# HokuyoPoE.net
KiCad netlist of a schematic drawn in EAGLE
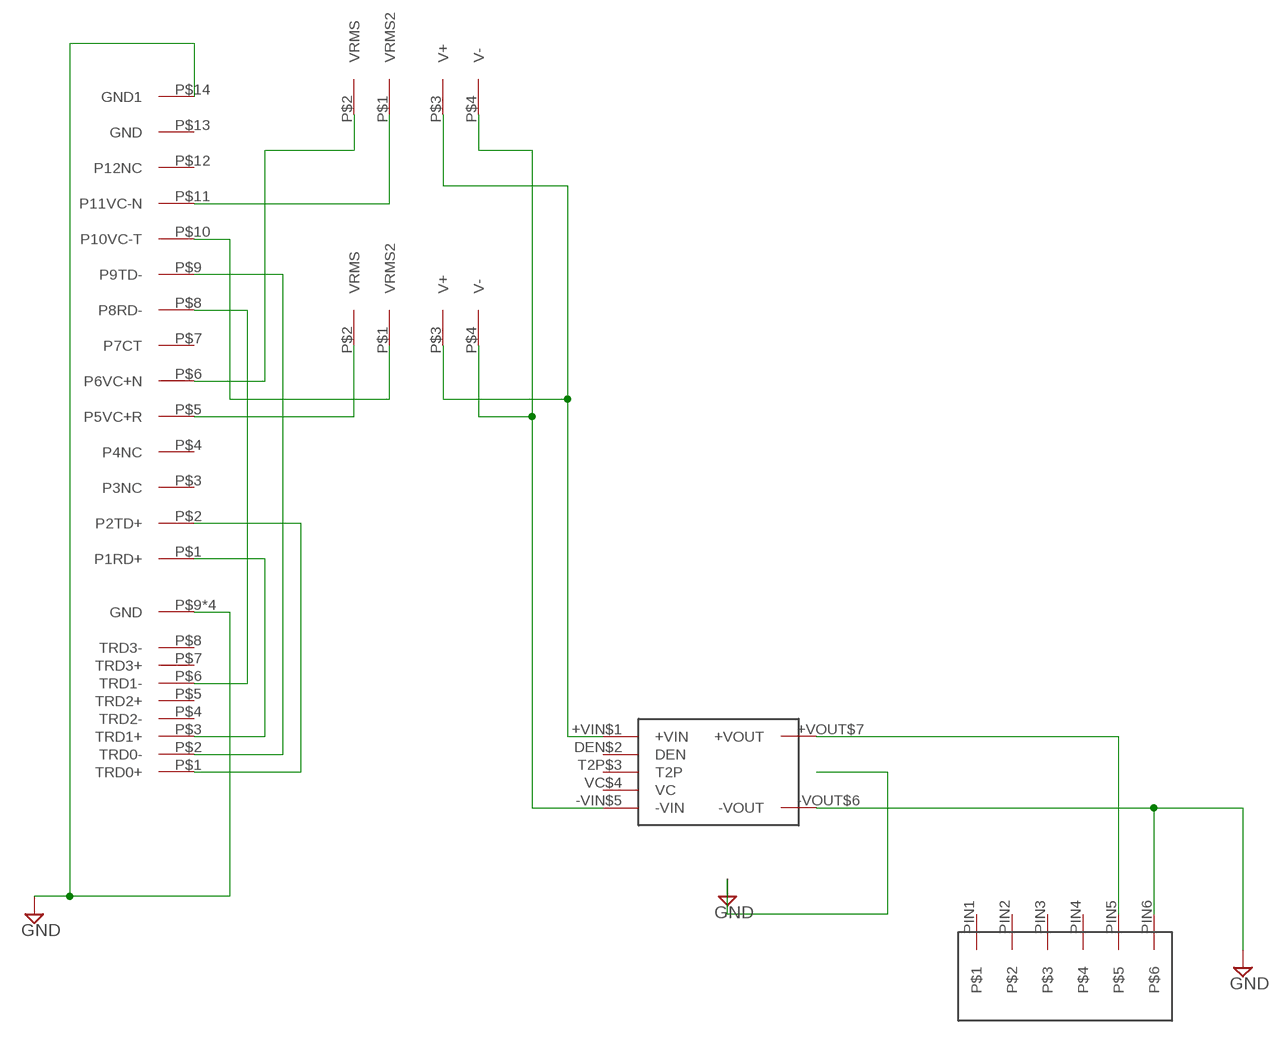
[diagram p0: schematic, sheet 1]

(export (version "E")
  (design (tool "Eeschema 10.0.6"))
  (components
    (comp (ref "U$1")
      (value "MYBSP0122BABFT")
      (footprint "eagle-import:MYBSP0122BABFT")
      (libsource (lib "eagle-import") (part "MYBSP0122BABFT"))
    )
    (comp (ref "U$2")
      (value "7810-XPXC[RJ45]")
      (footprint "eagle-import:7810-XPXC[RJ45]")
      (libsource (lib "eagle-import") (part "7810-XPXC[RJ45]"))
    )
    (comp (ref "U$3")
      (value "B1010S")
      (footprint "eagle-import:B1010S")
      (libsource (lib "eagle-import") (part "B1010S"))
    )
    (comp (ref "U$4")
      (value "SM08B-SRSS-TB")
      (footprint "eagle-import:SM08B-SRSS-TB")
      (libsource (lib "eagle-import") (part "SM08B-SRSS-TB"))
    )
    (comp (ref "U$5")
      (value "0813-1X1T-57-F")
      (footprint "eagle-import:0813-1X1T-57-F")
      (libsource (lib "eagle-import") (part "0813-1X1T-57-F"))
    )
    (comp (ref "U$6")
      (value "B1010S")
      (footprint "eagle-import:B1010S")
      (libsource (lib "eagle-import") (part "B1010S"))
    )
  )
  (nets
    (net (code "1") (name "GND") (class "Default")
      (node (ref "U$1") (pin "-VOUT$6") (pinfunction "-VOUT_-VOUT$6") (pintype "input"))
      (node (ref "U$2") (pin "P$10") (pinfunction "GND_P$10") (pintype "bidirectional"))
      (node (ref "U$2") (pin "P$11") (pinfunction "GND_P$11") (pintype "bidirectional"))
      (node (ref "U$2") (pin "P$12") (pinfunction "GND_P$12") (pintype "bidirectional"))
      (node (ref "U$2") (pin "P$9") (pinfunction "GND_P$9") (pintype "bidirectional"))
      (node (ref "U$4") (pin "PIN6") (pinfunction "P$6_PIN6") (pintype "bidirectional"))
      (node (ref "U$5") (pin "P$14") (pinfunction "GND1_P$14") (pintype "bidirectional"))
    )
    (net (code "2") (name "Net-(U$1-+VIN)") (class "Default")
      (node (ref "U$1") (pin "+VIN$1") (pinfunction "+VIN_+VIN$1") (pintype "input"))
      (node (ref "U$3") (pin "P$3") (pinfunction "V+_P$3") (pintype "bidirectional"))
      (node (ref "U$6") (pin "P$3") (pinfunction "V+_P$3") (pintype "bidirectional"))
    )
    (net (code "3") (name "Net-(U$1-+VOUT)") (class "Default")
      (node (ref "U$1") (pin "+VOUT$7") (pinfunction "+VOUT_+VOUT$7") (pintype "output"))
      (node (ref "U$4") (pin "PIN5") (pinfunction "P$5_PIN5") (pintype "bidirectional"))
    )
    (net (code "4") (name "Net-(U$1--VIN)") (class "Default")
      (node (ref "U$1") (pin "-VIN$5") (pinfunction "-VIN_-VIN$5") (pintype "input"))
      (node (ref "U$3") (pin "P$4") (pinfunction "V-_P$4") (pintype "bidirectional"))
      (node (ref "U$6") (pin "P$4") (pinfunction "V-_P$4") (pintype "bidirectional"))
    )
    (net (code "5") (name "Net-(U$2-TRD0+)") (class "Default")
      (node (ref "U$2") (pin "P$1") (pinfunction "TRD0+_P$1") (pintype "bidirectional"))
      (node (ref "U$5") (pin "P$2") (pinfunction "P2TD+_P$2") (pintype "bidirectional"))
    )
    (net (code "6") (name "Net-(U$2-TRD0-)") (class "Default")
      (node (ref "U$2") (pin "P$2") (pinfunction "TRD0-_P$2") (pintype "bidirectional"))
      (node (ref "U$5") (pin "P$9") (pinfunction "P9TD-_P$9") (pintype "bidirectional"))
    )
    (net (code "7") (name "Net-(U$2-TRD1+)") (class "Default")
      (node (ref "U$2") (pin "P$3") (pinfunction "TRD1+_P$3") (pintype "bidirectional"))
      (node (ref "U$5") (pin "P$1") (pinfunction "P1RD+_P$1") (pintype "bidirectional"))
    )
    (net (code "8") (name "Net-(U$2-TRD1-)") (class "Default")
      (node (ref "U$2") (pin "P$6") (pinfunction "TRD1-_P$6") (pintype "bidirectional"))
      (node (ref "U$5") (pin "P$8") (pinfunction "P8RD-_P$8") (pintype "bidirectional"))
    )
    (net (code "9") (name "Net-(U$3-VRMS)") (class "Default")
      (node (ref "U$3") (pin "P$2") (pinfunction "VRMS_P$2") (pintype "bidirectional"))
      (node (ref "U$5") (pin "P$6") (pinfunction "P6VC+N_P$6") (pintype "bidirectional"))
    )
    (net (code "10") (name "Net-(U$3-VRMS2)") (class "Default")
      (node (ref "U$3") (pin "P$1") (pinfunction "VRMS2_P$1") (pintype "bidirectional"))
      (node (ref "U$5") (pin "P$11") (pinfunction "P11VC-N_P$11") (pintype "bidirectional"))
    )
    (net (code "11") (name "Net-(U$5-P5VC+R)") (class "Default")
      (node (ref "U$5") (pin "P$5") (pinfunction "P5VC+R_P$5") (pintype "bidirectional"))
      (node (ref "U$6") (pin "P$2") (pinfunction "VRMS_P$2") (pintype "bidirectional"))
    )
    (net (code "12") (name "Net-(U$5-P10VC-T)") (class "Default")
      (node (ref "U$5") (pin "P$10") (pinfunction "P10VC-T_P$10") (pintype "bidirectional"))
      (node (ref "U$6") (pin "P$1") (pinfunction "VRMS2_P$1") (pintype "bidirectional"))
    )
    (net (code "13") (name "unconnected-(U$1-DEN-PadDEN$2)") (class "Default")
      (node (ref "U$1") (pin "DEN$2") (pinfunction "DEN_DEN$2") (pintype "bidirectional"))
    )
    (net (code "14") (name "unconnected-(U$1-T2P-PadT2P$3)") (class "Default")
      (node (ref "U$1") (pin "T2P$3") (pinfunction "T2P_T2P$3") (pintype "bidirectional"))
    )
    (net (code "15") (name "unconnected-(U$1-VC-PadVC$4)") (class "Default")
      (node (ref "U$1") (pin "VC$4") (pinfunction "VC_VC$4") (pintype "bidirectional"))
    )
    (net (code "16") (name "unconnected-(U$2-TRD2+-PadP$5)") (class "Default")
      (node (ref "U$2") (pin "P$5") (pinfunction "TRD2+_P$5") (pintype "bidirectional"))
    )
    (net (code "17") (name "unconnected-(U$2-TRD2--PadP$4)") (class "Default")
      (node (ref "U$2") (pin "P$4") (pinfunction "TRD2-_P$4") (pintype "bidirectional"))
    )
    (net (code "18") (name "unconnected-(U$2-TRD3+-PadP$7)") (class "Default")
      (node (ref "U$2") (pin "P$7") (pinfunction "TRD3+_P$7") (pintype "bidirectional"))
    )
    (net (code "19") (name "unconnected-(U$2-TRD3--PadP$8)") (class "Default")
      (node (ref "U$2") (pin "P$8") (pinfunction "TRD3-_P$8") (pintype "bidirectional"))
    )
    (net (code "20") (name "unconnected-(U$4-P$1-PadPIN1)") (class "Default")
      (node (ref "U$4") (pin "PIN1") (pinfunction "P$1_PIN1") (pintype "bidirectional"))
    )
    (net (code "21") (name "unconnected-(U$4-P$2-PadPIN2)") (class "Default")
      (node (ref "U$4") (pin "PIN2") (pinfunction "P$2_PIN2") (pintype "bidirectional"))
    )
    (net (code "22") (name "unconnected-(U$4-P$3-PadPIN3)") (class "Default")
      (node (ref "U$4") (pin "PIN3") (pinfunction "P$3_PIN3") (pintype "bidirectional"))
    )
    (net (code "23") (name "unconnected-(U$4-P$4-PadPIN4)") (class "Default")
      (node (ref "U$4") (pin "PIN4") (pinfunction "P$4_PIN4") (pintype "bidirectional"))
    )
    (net (code "24") (name "unconnected-(U$5-GND-PadP$13)") (class "Default")
      (node (ref "U$5") (pin "P$13") (pinfunction "GND_P$13") (pintype "bidirectional"))
    )
    (net (code "25") (name "unconnected-(U$5-P3NC-PadP$3)") (class "Default")
      (node (ref "U$5") (pin "P$3") (pinfunction "P3NC_P$3") (pintype "bidirectional"))
    )
    (net (code "26") (name "unconnected-(U$5-P4NC-PadP$4)") (class "Default")
      (node (ref "U$5") (pin "P$4") (pinfunction "P4NC_P$4") (pintype "bidirectional"))
    )
    (net (code "27") (name "unconnected-(U$5-P7CT-PadP$7)") (class "Default")
      (node (ref "U$5") (pin "P$7") (pinfunction "P7CT_P$7") (pintype "bidirectional"))
    )
    (net (code "28") (name "unconnected-(U$5-P12NC-PadP$12)") (class "Default")
      (node (ref "U$5") (pin "P$12") (pinfunction "P12NC_P$12") (pintype "bidirectional"))
    )
  )
)
